# solderstation_v1_6.net
KiCad netlist of a schematic drawn in EAGLE
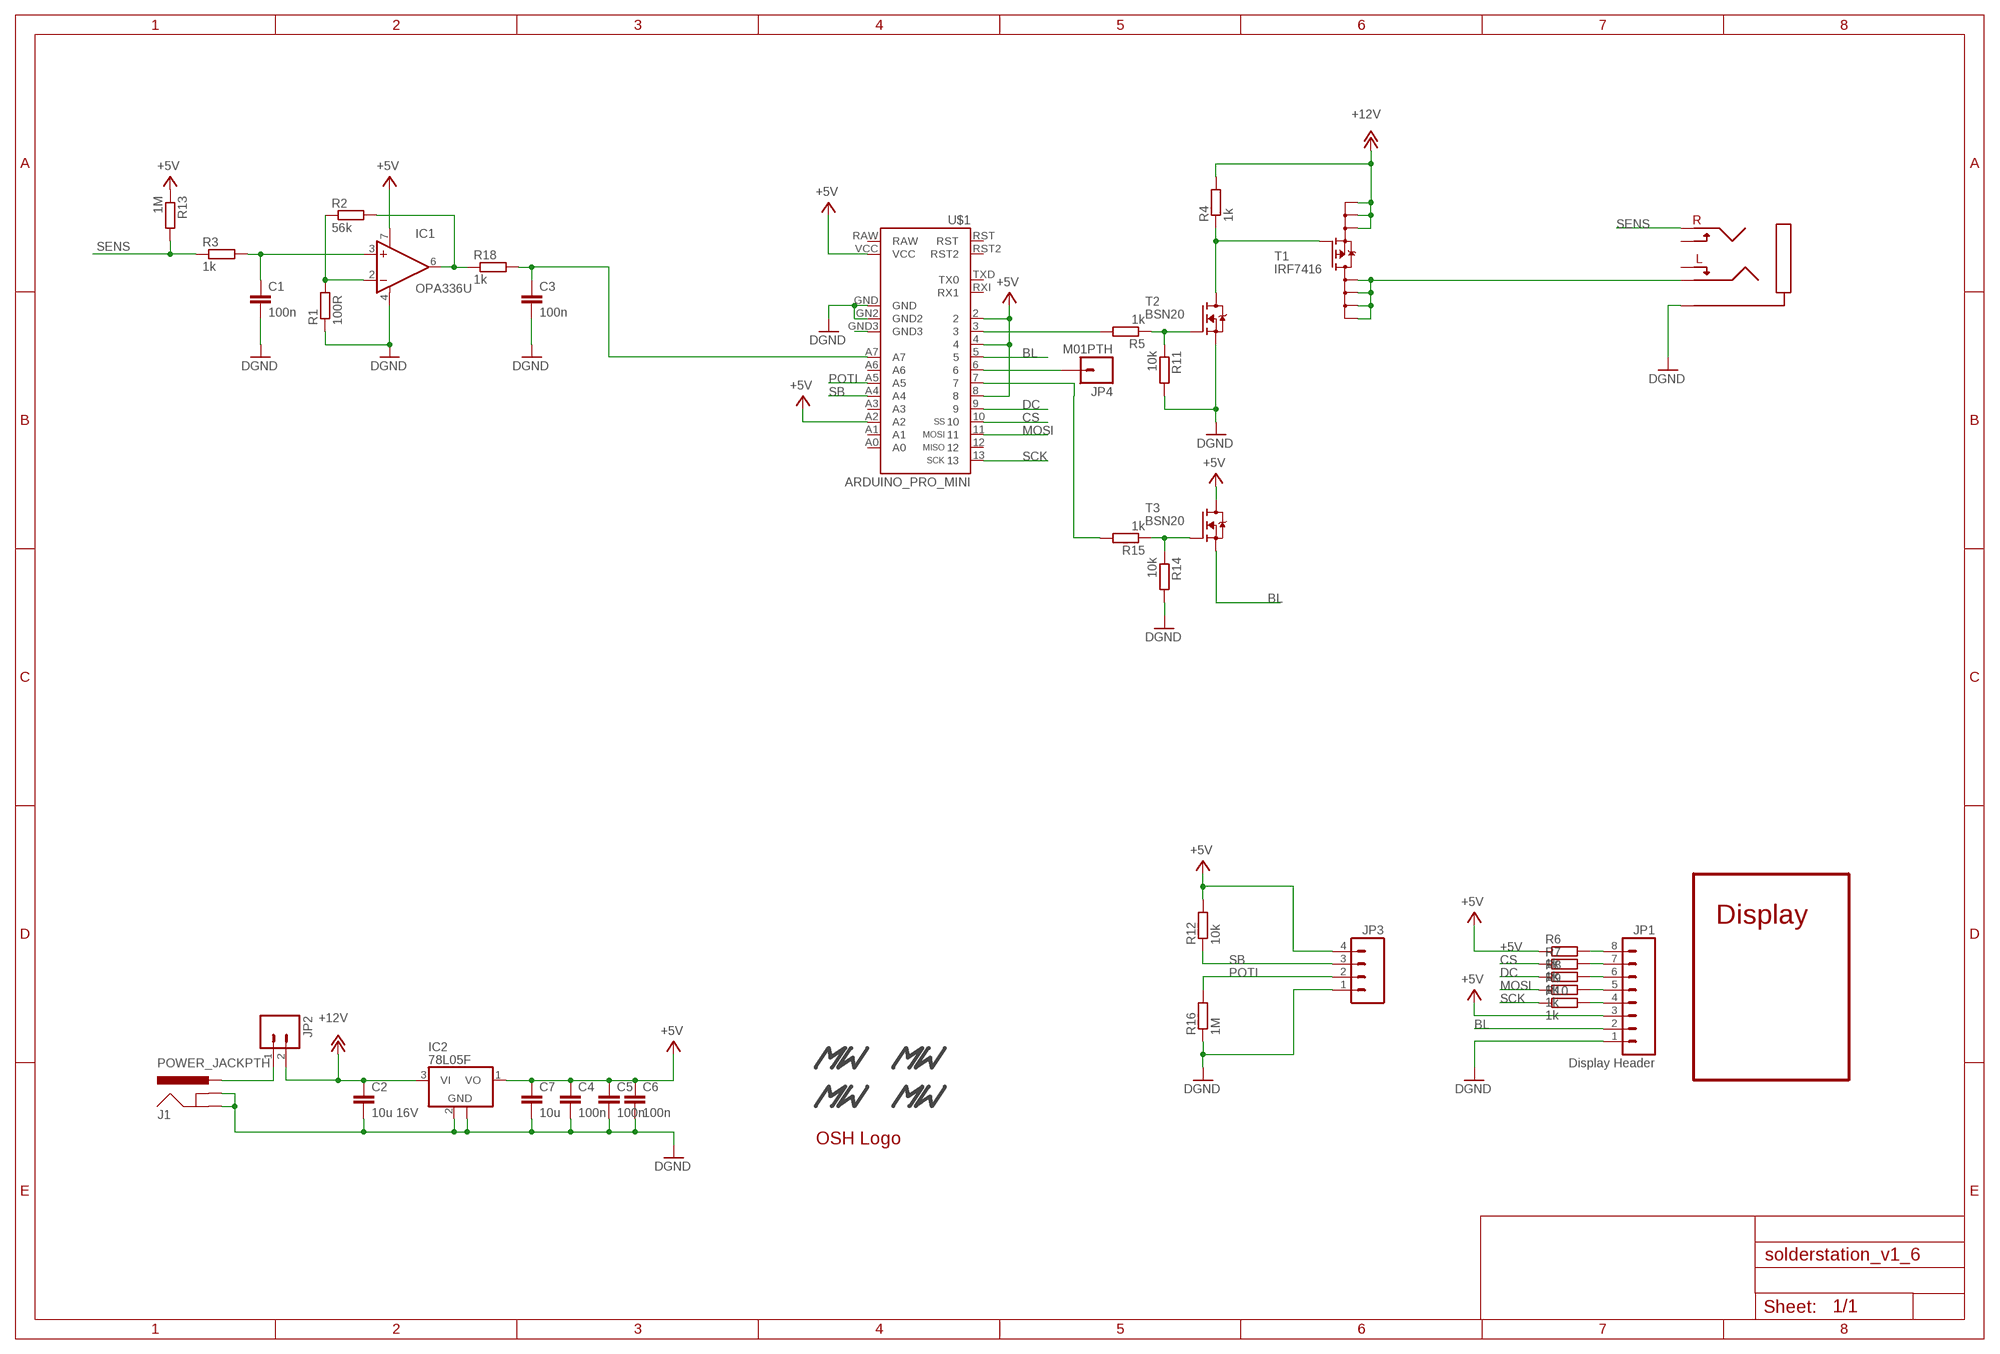
[diagram p0: schematic, sheet 1]

(export (version "E")
  (design (tool "Eeschema 10.0.6"))
  (components
    (comp (ref "C1")
      (value "100n")
      (footprint "eagle-import:C0603")
      (libsource (lib "eagle-import") (part "C-EUC0603"))
    )
    (comp (ref "C2")
      (value "10u 16V")
      (footprint "eagle-import:C1206")
      (libsource (lib "eagle-import") (part "C-EUC1206"))
    )
    (comp (ref "C3")
      (value "100n")
      (footprint "eagle-import:C0603")
      (libsource (lib "eagle-import") (part "C-EUC0603"))
    )
    (comp (ref "C4")
      (value "100n")
      (footprint "eagle-import:C0603")
      (libsource (lib "eagle-import") (part "C-EUC0603"))
    )
    (comp (ref "C5")
      (value "100n")
      (footprint "eagle-import:C0603")
      (libsource (lib "eagle-import") (part "C-EUC0603"))
    )
    (comp (ref "C6")
      (value "100n")
      (footprint "eagle-import:C0603")
      (libsource (lib "eagle-import") (part "C-EUC0603"))
    )
    (comp (ref "C7")
      (value "10u")
      (footprint "eagle-import:C1206")
      (libsource (lib "eagle-import") (part "C-EUC1206"))
    )
    (comp (ref "IC1")
      (value "OPA336U")
      (footprint "eagle-import:SO08")
      (fields (field (name "MF") "TEXAS INSTRUMENT CONNECTORS") (field (name "MPN") "OPA336UA"))
      (libsource (lib "eagle-import") (part "OPA336U"))
    )
    (comp (ref "IC2")
      (value "78L05F")
      (footprint "eagle-import:SOT89")
      (libsource (lib "eagle-import") (part "78LF05"))
    )
    (comp (ref "J1")
      (value "POWER_JACKPTH")
      (footprint "eagle-import:POWER_JACK_PTH")
      (libsource (lib "eagle-import") (part "POWER_JACKPTH"))
    )
    (comp (ref "JP1")
      (value "Display Header")
      (footprint "eagle-import:1X08_LOCK")
      (libsource (lib "eagle-import") (part "M08LOCK"))
    )
    (comp (ref "JP2")
      (value "M02LOCK_LONGPADS")
      (footprint "eagle-import:1X02_LOCK_LONGPADS")
      (libsource (lib "eagle-import") (part "M02LOCK_LONGPADS"))
    )
    (comp (ref "JP3")
      (value "M04LOCK")
      (footprint "eagle-import:1X04_LOCK")
      (libsource (lib "eagle-import") (part "M04LOCK"))
    )
    (comp (ref "JP4")
      (value "M01PTH")
      (footprint "eagle-import:1X01")
      (libsource (lib "eagle-import") (part "M01PTH"))
    )
    (comp (ref "R1")
      (value "100R")
      (footprint "eagle-import:R0603")
      (libsource (lib "eagle-import") (part "R-EU_R0603"))
    )
    (comp (ref "R2")
      (value "56k")
      (footprint "eagle-import:R0603")
      (libsource (lib "eagle-import") (part "R-EU_R0603"))
    )
    (comp (ref "R3")
      (value "1k")
      (footprint "eagle-import:R0603")
      (libsource (lib "eagle-import") (part "R-EU_R0603"))
    )
    (comp (ref "R4")
      (value "1k")
      (footprint "eagle-import:R0603")
      (libsource (lib "eagle-import") (part "R-EU_R0603"))
    )
    (comp (ref "R5")
      (value "1k")
      (footprint "eagle-import:R0603")
      (libsource (lib "eagle-import") (part "R-EU_R0603"))
    )
    (comp (ref "R6")
      (value "1k")
      (footprint "eagle-import:R0603")
      (libsource (lib "eagle-import") (part "R-EU_R0603"))
    )
    (comp (ref "R7")
      (value "1k")
      (footprint "eagle-import:R0603")
      (libsource (lib "eagle-import") (part "R-EU_R0603"))
    )
    (comp (ref "R8")
      (value "1k")
      (footprint "eagle-import:R0603")
      (libsource (lib "eagle-import") (part "R-EU_R0603"))
    )
    (comp (ref "R9")
      (value "1k")
      (footprint "eagle-import:R0603")
      (libsource (lib "eagle-import") (part "R-EU_R0603"))
    )
    (comp (ref "R10")
      (value "1k")
      (footprint "eagle-import:R0603")
      (libsource (lib "eagle-import") (part "R-EU_R0603"))
    )
    (comp (ref "R11")
      (value "10k")
      (footprint "eagle-import:R0603")
      (libsource (lib "eagle-import") (part "R-EU_R0603"))
    )
    (comp (ref "R12")
      (value "10k")
      (footprint "eagle-import:R0603")
      (libsource (lib "eagle-import") (part "R-EU_R0603"))
    )
    (comp (ref "R13")
      (value "1M")
      (footprint "eagle-import:R0603")
      (libsource (lib "eagle-import") (part "R-EU_R0603"))
    )
    (comp (ref "R14")
      (value "10k")
      (footprint "eagle-import:R0603")
      (libsource (lib "eagle-import") (part "R-EU_R0603"))
    )
    (comp (ref "R15")
      (value "1k")
      (footprint "eagle-import:R0603")
      (libsource (lib "eagle-import") (part "R-EU_R0603"))
    )
    (comp (ref "R16")
      (value "1M")
      (footprint "eagle-import:R0603")
      (libsource (lib "eagle-import") (part "R-EU_R0603"))
    )
    (comp (ref "R18")
      (value "1k")
      (footprint "eagle-import:R0603")
      (libsource (lib "eagle-import") (part "R-EU_R0603"))
    )
    (comp (ref "T1")
      (value "IRF7416")
      (footprint "eagle-import:SO8")
      (libsource (lib "eagle-import") (part "IRF7416"))
    )
    (comp (ref "T2")
      (value "BSN20")
      (footprint "eagle-import:SOT23")
      (libsource (lib "eagle-import") (part "BSN20"))
    )
    (comp (ref "T3")
      (value "BSN20")
      (footprint "eagle-import:SOT23")
      (libsource (lib "eagle-import") (part "BSN20"))
    )
    (comp (ref "U$1")
      (value "ARDUINO_PRO_MINI")
      (footprint "eagle-import:ARDUINO_PRO_MINI")
      (libsource (lib "eagle-import") (part "ARDUINO_PRO_MINI"))
    )
    (comp (ref "U$2")
      (value "AUDIO_JACK_3,5MMCONRAD")
      (footprint "eagle-import:AUDIO_JACK_3,5MM_CONRAD")
      (libsource (lib "eagle-import") (part "AUDIO_JACK_3,5MMCONRAD"))
    )
    (comp (ref "U$3")
      (value "MW_LOGO")
      (footprint "eagle-import:MW_11X5MM")
      (libsource (lib "eagle-import") (part "MW_LOGO"))
    )
    (comp (ref "U$4")
      (value "MW_LOGO_SOLDER")
      (footprint "eagle-import:MW_11X5MM_SOLDER")
      (libsource (lib "eagle-import") (part "MW_LOGO_SOLDER"))
    )
    (comp (ref "U$5")
      (value "MW_LOGO")
      (footprint "eagle-import:MW_11X5MM")
      (libsource (lib "eagle-import") (part "MW_LOGO"))
    )
    (comp (ref "U$8")
      (value "OSH_LOGOS")
      (footprint "eagle-import:OSH_LOGO_S")
      (libsource (lib "eagle-import") (part "OSH_LOGOS"))
    )
    (comp (ref "U$9")
      (value "MW_LOGO_SOLDER")
      (footprint "eagle-import:MW_11X5MM_SOLDER")
      (libsource (lib "eagle-import") (part "MW_LOGO_SOLDER"))
    )
  )
  (nets
    (net (code "1") (name "+5V") (class "Default")
      (node (ref "C4") (pin "1") (pinfunction "1_1") (pintype "passive"))
      (node (ref "C5") (pin "1") (pinfunction "1_1") (pintype "passive"))
      (node (ref "C6") (pin "1") (pinfunction "1_1") (pintype "passive"))
      (node (ref "C7") (pin "1") (pinfunction "1_1") (pintype "passive"))
      (node (ref "IC1") (pin "7") (pinfunction "V+_7") (pintype "power_in"))
      (node (ref "IC2") (pin "1") (pinfunction "VO_1") (pintype "passive"))
      (node (ref "JP1") (pin "3") (pinfunction "3_3") (pintype "passive"))
      (node (ref "JP3") (pin "4") (pinfunction "4_4") (pintype "passive"))
      (node (ref "R12") (pin "2") (pinfunction "2_2") (pintype "passive"))
      (node (ref "R13") (pin "1") (pinfunction "1_1") (pintype "passive"))
      (node (ref "R6") (pin "1") (pinfunction "1_1") (pintype "passive"))
      (node (ref "T3") (pin "3") (pinfunction "D_3") (pintype "passive"))
      (node (ref "U$1") (pin "2") (pinfunction "2_2") (pintype "bidirectional"))
      (node (ref "U$1") (pin "4") (pinfunction "4_4") (pintype "bidirectional"))
      (node (ref "U$1") (pin "8") (pinfunction "8_8") (pintype "bidirectional"))
      (node (ref "U$1") (pin "A2") (pinfunction "A2_A2") (pintype "bidirectional"))
      (node (ref "U$1") (pin "VCC") (pinfunction "VCC_VCC") (pintype "bidirectional"))
    )
    (net (code "2") (name "+12V") (class "Default")
      (node (ref "C2") (pin "1") (pinfunction "1_1") (pintype "passive"))
      (node (ref "IC2") (pin "3") (pinfunction "VI_3") (pintype "input"))
      (node (ref "JP2") (pin "2") (pinfunction "2_2") (pintype "passive"))
      (node (ref "R4") (pin "2") (pinfunction "2_2") (pintype "passive"))
      (node (ref "T1") (pin "1") (pinfunction "S0_1") (pintype "passive"))
      (node (ref "T1") (pin "2") (pinfunction "S1_2") (pintype "passive"))
      (node (ref "T1") (pin "3") (pinfunction "S2_3") (pintype "passive"))
    )
    (net (code "3") (name "/BL") (class "Default")
      (node (ref "JP1") (pin "2") (pinfunction "2_2") (pintype "passive"))
      (node (ref "T3") (pin "2") (pinfunction "S_2") (pintype "passive"))
      (node (ref "U$1") (pin "5") (pinfunction "5_5") (pintype "bidirectional"))
    )
    (net (code "4") (name "/CS") (class "Default")
      (node (ref "R7") (pin "1") (pinfunction "1_1") (pintype "passive"))
      (node (ref "U$1") (pin "10") (pinfunction "10_10") (pintype "bidirectional"))
    )
    (net (code "5") (name "/DC") (class "Default")
      (node (ref "R8") (pin "1") (pinfunction "1_1") (pintype "passive"))
      (node (ref "U$1") (pin "9") (pinfunction "9_9") (pintype "bidirectional"))
    )
    (net (code "6") (name "/MOSI") (class "Default")
      (node (ref "R9") (pin "1") (pinfunction "1_1") (pintype "passive"))
      (node (ref "U$1") (pin "11") (pinfunction "11_11") (pintype "bidirectional"))
    )
    (net (code "7") (name "/POTI") (class "Default")
      (node (ref "JP3") (pin "2") (pinfunction "2_2") (pintype "passive"))
      (node (ref "R16") (pin "2") (pinfunction "2_2") (pintype "passive"))
      (node (ref "U$1") (pin "A5") (pinfunction "A5_A5") (pintype "bidirectional"))
    )
    (net (code "8") (name "/SB") (class "Default")
      (node (ref "JP3") (pin "3") (pinfunction "3_3") (pintype "passive"))
      (node (ref "R12") (pin "1") (pinfunction "1_1") (pintype "passive"))
      (node (ref "U$1") (pin "A4") (pinfunction "A4_A4") (pintype "bidirectional"))
    )
    (net (code "9") (name "/SCK") (class "Default")
      (node (ref "R10") (pin "1") (pinfunction "1_1") (pintype "passive"))
      (node (ref "U$1") (pin "13") (pinfunction "13_13") (pintype "bidirectional"))
    )
    (net (code "10") (name "/SENS") (class "Default")
      (node (ref "R13") (pin "2") (pinfunction "2_2") (pintype "passive"))
      (node (ref "R3") (pin "1") (pinfunction "1_1") (pintype "passive"))
      (node (ref "U$2") (pin "P_RIGHT") (pinfunction "P$1_P_RIGHT") (pintype "bidirectional"))
    )
    (net (code "11") (name "DGND") (class "Default")
      (node (ref "C1") (pin "2") (pinfunction "2_2") (pintype "passive"))
      (node (ref "C2") (pin "2") (pinfunction "2_2") (pintype "passive"))
      (node (ref "C3") (pin "2") (pinfunction "2_2") (pintype "passive"))
      (node (ref "C4") (pin "2") (pinfunction "2_2") (pintype "passive"))
      (node (ref "C5") (pin "2") (pinfunction "2_2") (pintype "passive"))
      (node (ref "C6") (pin "2") (pinfunction "2_2") (pintype "passive"))
      (node (ref "C7") (pin "2") (pinfunction "2_2") (pintype "passive"))
      (node (ref "IC1") (pin "4") (pinfunction "V-_4") (pintype "power_in"))
      (node (ref "IC2") (pin "2") (pinfunction "GND_2") (pintype "passive"))
      (node (ref "IC2") (pin "2@1") (pinfunction "GND_2@1") (pintype "passive"))
      (node (ref "J1") (pin "GND") (pinfunction "GND_GND") (pintype "bidirectional"))
      (node (ref "J1") (pin "GNDBREAK") (pinfunction "GNDBREAK_GNDBREAK") (pintype "bidirectional"))
      (node (ref "JP1") (pin "1") (pinfunction "1_1") (pintype "passive"))
      (node (ref "JP3") (pin "1") (pinfunction "1_1") (pintype "passive"))
      (node (ref "R1") (pin "1") (pinfunction "1_1") (pintype "passive"))
      (node (ref "R11") (pin "2") (pinfunction "2_2") (pintype "passive"))
      (node (ref "R14") (pin "2") (pinfunction "2_2") (pintype "passive"))
      (node (ref "R16") (pin "1") (pinfunction "1_1") (pintype "passive"))
      (node (ref "T2") (pin "2") (pinfunction "S_2") (pintype "passive"))
      (node (ref "U$1") (pin "GN2") (pinfunction "GND2_GN2") (pintype "bidirectional"))
      (node (ref "U$1") (pin "GND") (pinfunction "GND_GND") (pintype "bidirectional"))
      (node (ref "U$2") (pin "P_GND") (pinfunction "P$5_P_GND") (pintype "bidirectional"))
    )
    (net (code "12") (name "Net-(C3-Pad1)") (class "Default")
      (node (ref "C3") (pin "1") (pinfunction "1_1") (pintype "passive"))
      (node (ref "R18") (pin "2") (pinfunction "2_2") (pintype "passive"))
      (node (ref "U$1") (pin "A7") (pinfunction "A7_A7") (pintype "bidirectional"))
    )
    (net (code "13") (name "Net-(IC1-+IN)") (class "Default")
      (node (ref "C1") (pin "1") (pinfunction "1_1") (pintype "passive"))
      (node (ref "IC1") (pin "3") (pinfunction "+IN_3") (pintype "input"))
      (node (ref "R3") (pin "2") (pinfunction "2_2") (pintype "passive"))
    )
    (net (code "14") (name "Net-(IC1--IN)") (class "Default")
      (node (ref "IC1") (pin "2") (pinfunction "-IN_2") (pintype "input"))
      (node (ref "R1") (pin "2") (pinfunction "2_2") (pintype "passive"))
      (node (ref "R2") (pin "1") (pinfunction "1_1") (pintype "passive"))
    )
    (net (code "15") (name "Net-(IC1-OUT)") (class "Default")
      (node (ref "IC1") (pin "6") (pinfunction "OUT_6") (pintype "output"))
      (node (ref "R18") (pin "1") (pinfunction "1_1") (pintype "passive"))
      (node (ref "R2") (pin "2") (pinfunction "2_2") (pintype "passive"))
    )
    (net (code "16") (name "Net-(J1-PadPWR)") (class "Default")
      (node (ref "J1") (pin "PWR") (pinfunction "PWR_PWR") (pintype "bidirectional"))
      (node (ref "JP2") (pin "1") (pinfunction "1_1") (pintype "passive"))
    )
    (net (code "17") (name "Net-(JP1-Pad4)") (class "Default")
      (node (ref "JP1") (pin "4") (pinfunction "4_4") (pintype "passive"))
      (node (ref "R10") (pin "2") (pinfunction "2_2") (pintype "passive"))
    )
    (net (code "18") (name "Net-(JP1-Pad5)") (class "Default")
      (node (ref "JP1") (pin "5") (pinfunction "5_5") (pintype "passive"))
      (node (ref "R9") (pin "2") (pinfunction "2_2") (pintype "passive"))
    )
    (net (code "19") (name "Net-(JP1-Pad6)") (class "Default")
      (node (ref "JP1") (pin "6") (pinfunction "6_6") (pintype "passive"))
      (node (ref "R8") (pin "2") (pinfunction "2_2") (pintype "passive"))
    )
    (net (code "20") (name "Net-(JP1-Pad7)") (class "Default")
      (node (ref "JP1") (pin "7") (pinfunction "7_7") (pintype "passive"))
      (node (ref "R7") (pin "2") (pinfunction "2_2") (pintype "passive"))
    )
    (net (code "21") (name "Net-(JP1-Pad8)") (class "Default")
      (node (ref "JP1") (pin "8") (pinfunction "8_8") (pintype "passive"))
      (node (ref "R6") (pin "2") (pinfunction "2_2") (pintype "passive"))
    )
    (net (code "22") (name "Net-(JP4-Pad1)") (class "Default")
      (node (ref "JP4") (pin "1") (pinfunction "1_1") (pintype "passive"))
      (node (ref "U$1") (pin "6") (pinfunction "6_6") (pintype "bidirectional"))
    )
    (net (code "23") (name "Net-(R5-Pad2)") (class "Default")
      (node (ref "R5") (pin "2") (pinfunction "2_2") (pintype "passive"))
      (node (ref "U$1") (pin "3") (pinfunction "3_3") (pintype "bidirectional"))
    )
    (net (code "24") (name "Net-(R15-Pad2)") (class "Default")
      (node (ref "R15") (pin "2") (pinfunction "2_2") (pintype "passive"))
      (node (ref "U$1") (pin "7") (pinfunction "7_7") (pintype "bidirectional"))
    )
    (net (code "25") (name "Net-(T1-D0)") (class "Default")
      (node (ref "T1") (pin "5") (pinfunction "D0_5") (pintype "passive"))
      (node (ref "T1") (pin "6") (pinfunction "D1_6") (pintype "passive"))
      (node (ref "T1") (pin "7") (pinfunction "D2_7") (pintype "passive"))
      (node (ref "T1") (pin "8") (pinfunction "D3_8") (pintype "passive"))
      (node (ref "U$2") (pin "P_LEFT") (pinfunction "P$4_P_LEFT") (pintype "bidirectional"))
    )
    (net (code "26") (name "Net-(T1-G)") (class "Default")
      (node (ref "R4") (pin "1") (pinfunction "1_1") (pintype "passive"))
      (node (ref "T1") (pin "4") (pinfunction "G_4") (pintype "passive"))
      (node (ref "T2") (pin "3") (pinfunction "D_3") (pintype "passive"))
    )
    (net (code "27") (name "Net-(T2-G)") (class "Default")
      (node (ref "R11") (pin "1") (pinfunction "1_1") (pintype "passive"))
      (node (ref "R5") (pin "1") (pinfunction "1_1") (pintype "passive"))
      (node (ref "T2") (pin "1") (pinfunction "G_1") (pintype "passive"))
    )
    (net (code "28") (name "Net-(T3-G)") (class "Default")
      (node (ref "R14") (pin "1") (pinfunction "1_1") (pintype "passive"))
      (node (ref "R15") (pin "1") (pinfunction "1_1") (pintype "passive"))
      (node (ref "T3") (pin "1") (pinfunction "G_1") (pintype "passive"))
    )
    (net (code "29") (name "unconnected-(U$1-Pad12)") (class "Default")
      (node (ref "U$1") (pin "12") (pinfunction "12_12") (pintype "bidirectional"))
    )
    (net (code "30") (name "unconnected-(U$1-PadA0)") (class "Default")
      (node (ref "U$1") (pin "A0") (pinfunction "A0_A0") (pintype "bidirectional"))
    )
    (net (code "31") (name "unconnected-(U$1-PadA1)") (class "Default")
      (node (ref "U$1") (pin "A1") (pinfunction "A1_A1") (pintype "bidirectional"))
    )
    (net (code "32") (name "unconnected-(U$1-PadA3)") (class "Default")
      (node (ref "U$1") (pin "A3") (pinfunction "A3_A3") (pintype "bidirectional"))
    )
    (net (code "33") (name "unconnected-(U$1-PadA6)") (class "Default")
      (node (ref "U$1") (pin "A6") (pinfunction "A6_A6") (pintype "bidirectional"))
    )
    (net (code "34") (name "unconnected-(U$1-PadGND3)") (class "Default")
      (node (ref "U$1") (pin "GND3") (pinfunction "GND3_GND3") (pintype "bidirectional"))
    )
    (net (code "35") (name "unconnected-(U$1-PadRAW)") (class "Default")
      (node (ref "U$1") (pin "RAW") (pinfunction "RAW_RAW") (pintype "bidirectional"))
    )
    (net (code "36") (name "unconnected-(U$1-PadRST)") (class "Default")
      (node (ref "U$1") (pin "RST") (pinfunction "RST_RST") (pintype "bidirectional"))
    )
    (net (code "37") (name "unconnected-(U$1-PadRST2)") (class "Default")
      (node (ref "U$1") (pin "RST2") (pinfunction "RST2_RST2") (pintype "bidirectional"))
    )
    (net (code "38") (name "unconnected-(U$1-RX1-PadRXI)") (class "Default")
      (node (ref "U$1") (pin "RXI") (pinfunction "RX1_RXI") (pintype "bidirectional"))
    )
    (net (code "39") (name "unconnected-(U$1-TX0-PadTXD)") (class "Default")
      (node (ref "U$1") (pin "TXD") (pinfunction "TX0_TXD") (pintype "bidirectional"))
    )
    (net (code "40") (name "unconnected-(U$2-P$2-PadP_G_R)") (class "Default")
      (node (ref "U$2") (pin "P_G_R") (pinfunction "P$2_P_G_R") (pintype "bidirectional"))
    )
    (net (code "41") (name "unconnected-(U$2-P$3-PadP_G_L)") (class "Default")
      (node (ref "U$2") (pin "P_G_L") (pinfunction "P$3_P_G_L") (pintype "bidirectional"))
    )
  )
)
